# F1C100S-MY.net
KiCad netlist of a schematic drawn in Altium Designer
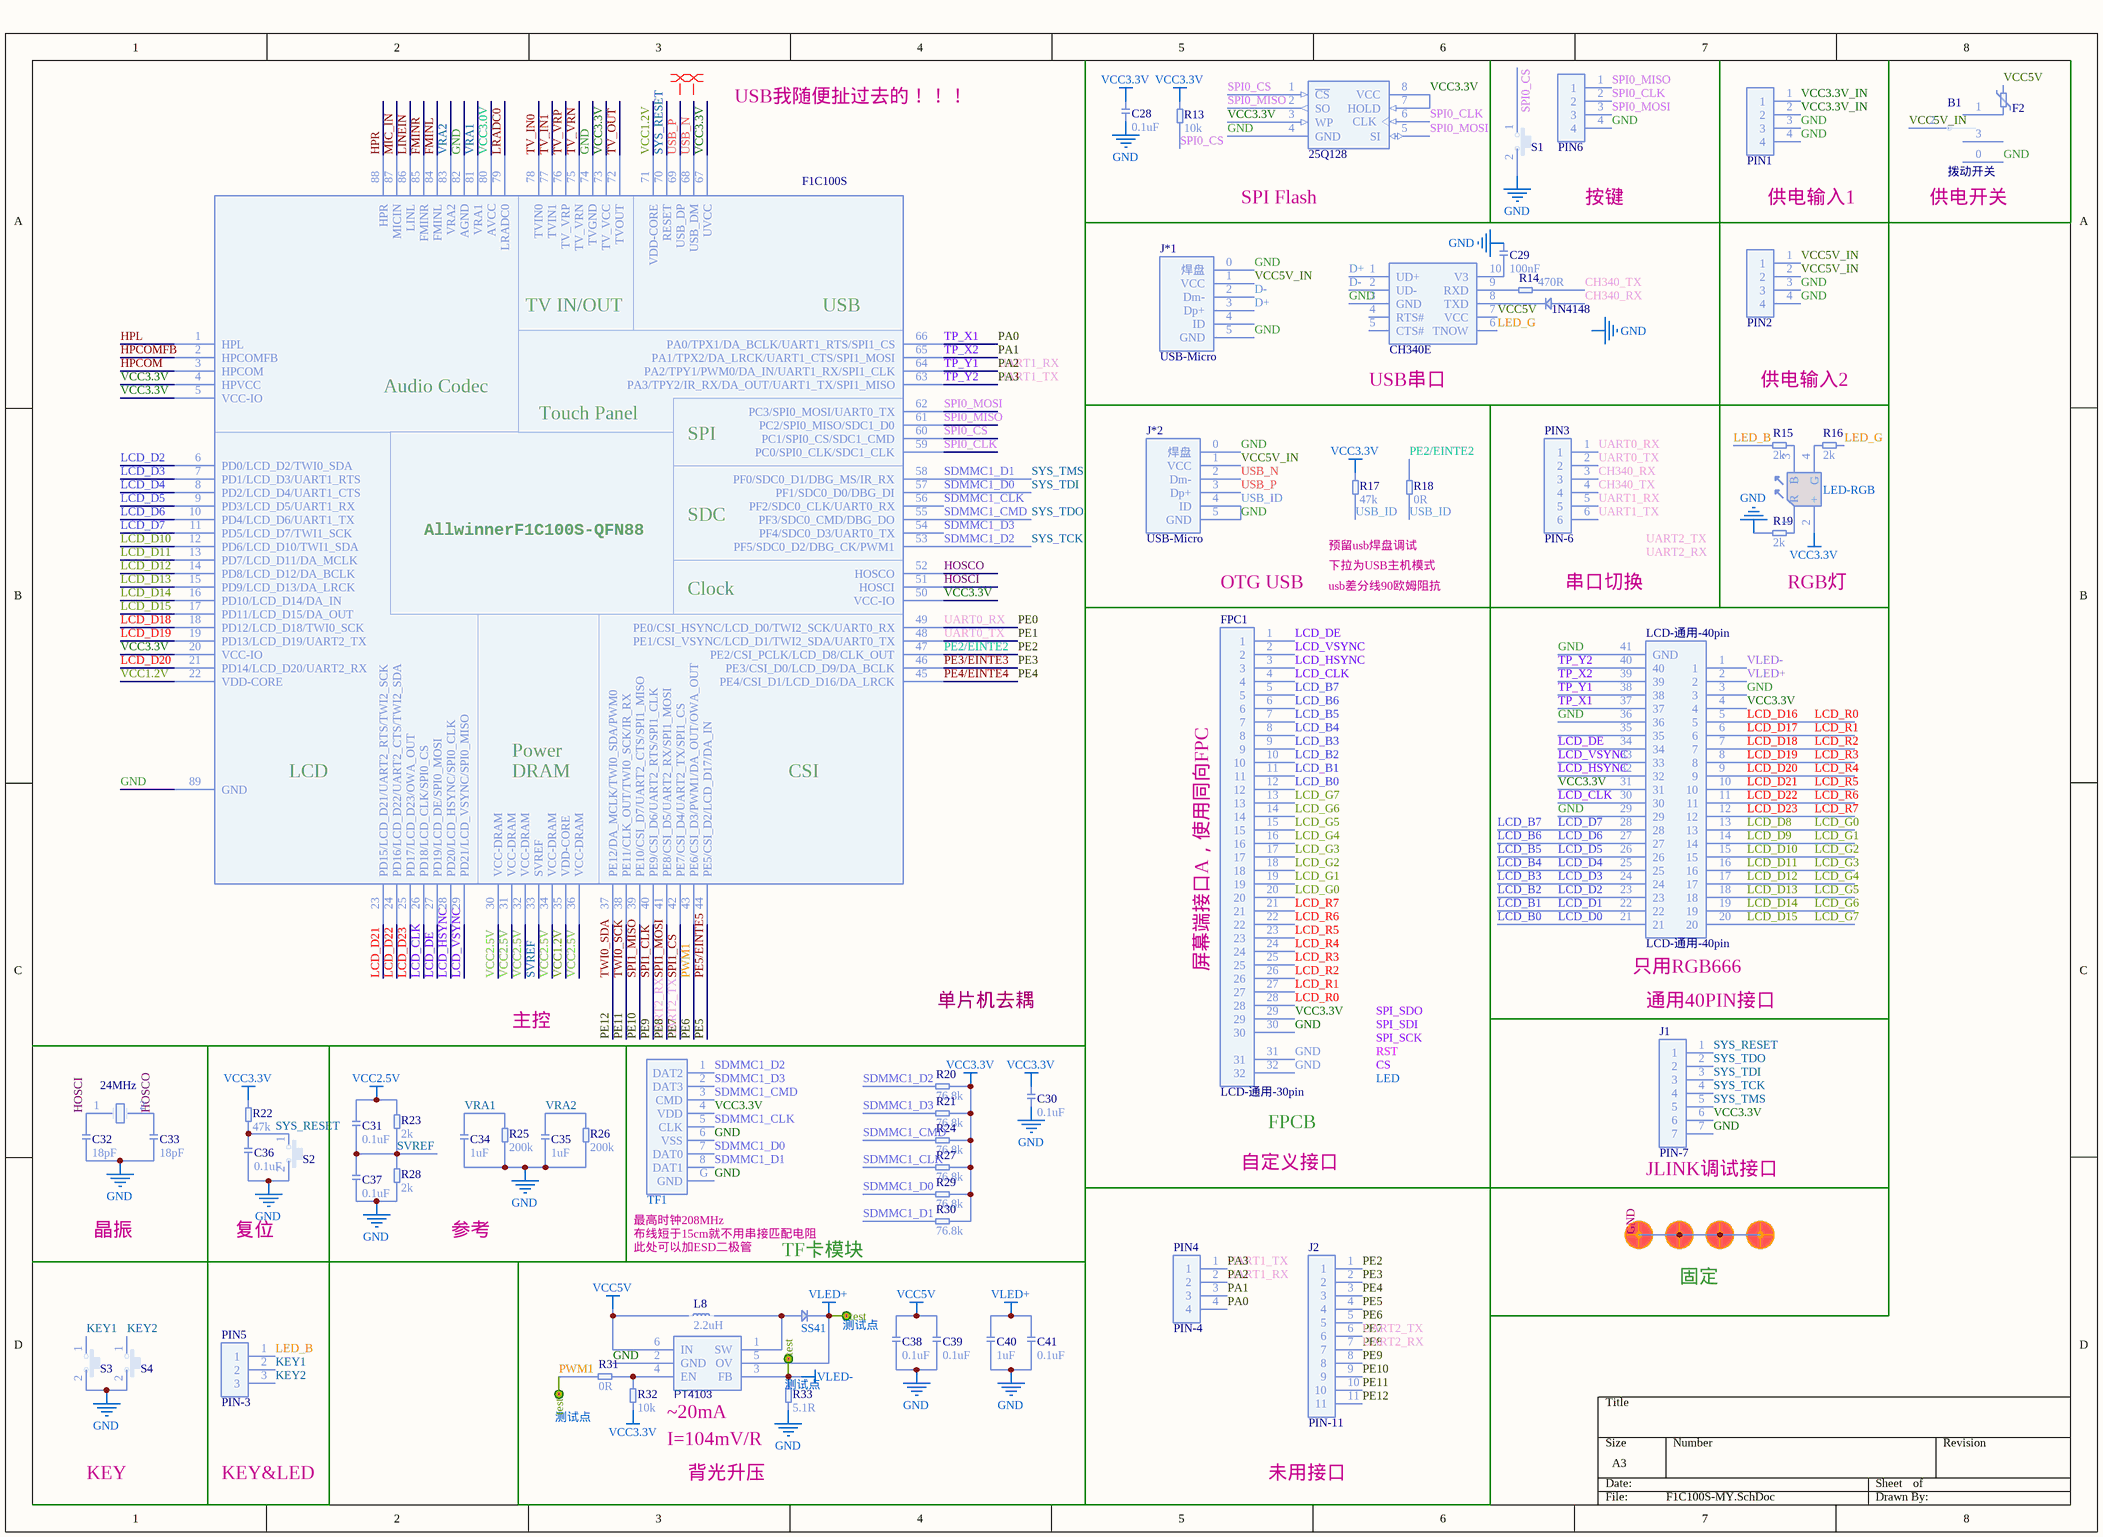
[diagram p0: F1C100S-MY.SchDoc]

(export (version "E")
  (design (tool "Eeschema 10.0.6"))
  (components
    (comp (ref "1N4148") (value "直插1N4148") (footprint "L0603") (libsource (lib "二极管") (part "直插1N4148")))
    (comp (ref "24MHz") (value "XTAL") (footprint "AT26-mini") (libsource (lib "晶振") (part "XTAL")))
    (comp (ref "25Q128")
      (value "25Qxx")
      (footprint "SOP-8M")
      (description "外置EEPROM")
      (libsource (lib "常用芯片") (part "25Qxx"))
    )
    (comp (ref "B1") (value "拨动开关") (footprint "开关:拨动开关-侧位-4.4X8.7MM") (libsource (lib "开关") (part "拨动开关")))
    (comp (ref "C28")
      (value "0.1uF")
      (footprint "0603C-mini")
      (fields (field (name "Comment") "非极性电容"))
      (libsource (lib "电容") (part "非极性电容"))
    )
    (comp (ref "C29")
      (value "100nF")
      (footprint "0603C-mini")
      (fields (field (name "Comment") "非极性电容"))
      (libsource (lib "电容") (part "非极性电容"))
    )
    (comp (ref "C30")
      (value "0.1uF")
      (footprint "0603C-mini")
      (fields (field (name "Comment") "非极性电容"))
      (libsource (lib "电容") (part "非极性电容"))
    )
    (comp (ref "C31")
      (value "0.1uF")
      (footprint "0603C-mini")
      (fields (field (name "Comment") "非极性电容"))
      (libsource (lib "电容") (part "非极性电容"))
    )
    (comp (ref "C32")
      (value "18pF")
      (footprint "0603C-mini")
      (fields (field (name "Comment") "非极性电容"))
      (libsource (lib "电容") (part "非极性电容"))
    )
    (comp (ref "C33")
      (value "18pF")
      (footprint "0603C-mini")
      (fields (field (name "Comment") "非极性电容"))
      (libsource (lib "电容") (part "非极性电容"))
    )
    (comp (ref "C34")
      (value "1uF")
      (footprint "0603C-mini")
      (fields (field (name "Comment") "非极性电容"))
      (libsource (lib "电容") (part "非极性电容"))
    )
    (comp (ref "C35")
      (value "1uF")
      (footprint "0603C-mini")
      (fields (field (name "Comment") "非极性电容"))
      (libsource (lib "电容") (part "非极性电容"))
    )
    (comp (ref "C36")
      (value "0.1uF")
      (footprint "0603C-mini")
      (fields (field (name "Comment") "非极性电容"))
      (libsource (lib "电容") (part "非极性电容"))
    )
    (comp (ref "C37")
      (value "0.1uF")
      (footprint "0603C-mini")
      (fields (field (name "Comment") "非极性电容"))
      (libsource (lib "电容") (part "非极性电容"))
    )
    (comp (ref "C38")
      (value "0.1uF")
      (footprint "0603C-mini")
      (fields (field (name "Comment") "非极性电容"))
      (libsource (lib "电容") (part "非极性电容"))
    )
    (comp (ref "C39")
      (value "0.1uF")
      (footprint "0603C-mini")
      (fields (field (name "Comment") "非极性电容"))
      (libsource (lib "电容") (part "非极性电容"))
    )
    (comp (ref "C40")
      (value "1uF")
      (footprint "0603C-mini")
      (fields (field (name "Comment") "非极性电容"))
      (libsource (lib "电容") (part "非极性电容"))
    )
    (comp (ref "C41")
      (value "0.1uF")
      (footprint "0603C-mini")
      (fields (field (name "Comment") "非极性电容"))
      (libsource (lib "电容") (part "非极性电容"))
    )
    (comp (ref "CH340E")
      (value "USB2UART_CH340E")
      (footprint "MSOP-10")
      (description "USB2UART")
      (libsource (lib "常用芯片") (part "USB2UART_CH340E"))
    )
    (comp (ref "F1C100S")
      (value "Allwinner-F1C100S")
      (footprint "QFN88")
      (libsource (lib "单片机") (part "Allwinner-F1C100S"))
    )
    (comp (ref "F2") (value "自恢复保险丝") (footprint "电阻:FU 0603") (libsource (lib "电阻") (part "自恢复保险丝")))
    (comp (ref "FPC1")
      (value "LCD-通用-30pin")
      (footprint "LCD-翻盖式-30PIN-0.5MM-2")
      (libsource (lib "LCD-通用") (part "LCD-通用-30pin"))
    )
    (comp (ref "J*1")
      (value "USB-Micro")
      (footprint "USB-MICRO贴片")
      (libsource (lib "接插件") (part "USB-Micro"))
    )
    (comp (ref "J*2")
      (value "USB-Micro")
      (footprint "USB-MICRO贴片")
      (libsource (lib "接插件") (part "USB-Micro"))
    )
    (comp (ref "J1") (value "PIN-7") (footprint "2.54排针1X7-标准") (libsource (lib "接插件") (part "PIN-7")))
    (comp (ref "J2") (value "PIN-11") (footprint "2.54排针1X11-标准") (libsource (lib "接插件") (part "PIN-11")))
    (comp (ref "J3") (value "定位孔") (footprint "定位孔 - 1.9MM") (libsource (lib "接插件") (part "定位孔")))
    (comp (ref "J4") (value "定位孔") (footprint "定位孔 - 1.9MM") (libsource (lib "接插件") (part "定位孔")))
    (comp (ref "J5") (value "定位孔") (footprint "定位孔 - 1.9MM") (libsource (lib "接插件") (part "定位孔")))
    (comp (ref "J6") (value "定位孔") (footprint "定位孔 - 1.9MM") (libsource (lib "接插件") (part "定位孔")))
    (comp (ref "L8")
      (value "2.2uH")
      (footprint "SMD-4.5x4.0x3.2mm")
      (fields (field (name "Comment") "贴片电感"))
      (libsource (lib "电感") (part "贴片电感"))
    )
    (comp (ref "LCD-通用-40pin")
      (value "LCD-通用-40pin")
      (footprint "LCD-翻盖式-40PIN-0.5MM-2")
      (libsource (lib "LCD-通用") (part "LCD-通用-40pin"))
    )
    (comp (ref "LED-RGB") (value "0606 RGB") (footprint "0606RGB") (libsource (lib "二极管") (part "0606 RGB")))
    (comp (ref "PIN1") (value "PIN-4") (footprint "2.54排针2X2-标准") (libsource (lib "接插件") (part "PIN-4")))
    (comp (ref "PIN2") (value "PIN-4") (footprint "2.54排针2X2-标准") (libsource (lib "接插件") (part "PIN-4")))
    (comp (ref "PIN3") (value "PIN-6") (footprint "2.54排针2X3-标准") (libsource (lib "接插件") (part "PIN-6")))
    (comp (ref "PIN4") (value "PIN-4") (footprint "2.54排针1X4-标准") (libsource (lib "接插件") (part "PIN-4")))
    (comp (ref "PIN5") (value "PIN-3") (footprint "2.54排针1X3-标准") (libsource (lib "接插件") (part "PIN-3")))
    (comp (ref "PIN6") (value "PIN-4") (footprint "2.54排针1X4-标准") (libsource (lib "接插件") (part "PIN-4")))
    (comp (ref "PT4103")
      (value "DCDC_PT4103")
      (footprint "SOT-23-6")
      (description "升压型DCDC")
      (libsource (lib "常用芯片") (part "DCDC_PT4103"))
    )
    (comp (ref "R13")
      (value "10k")
      (footprint "R0603-mini")
      (description "贴片电阻")
      (libsource (lib "") (part "贴片电阻_1"))
    )
    (comp (ref "R14")
      (value "470R")
      (footprint "R0603-mini")
      (description "贴片电阻")
      (libsource (lib "电阻") (part "贴片电阻"))
    )
    (comp (ref "R15")
      (value "2k")
      (footprint "R0603-mini")
      (description "贴片电阻")
      (libsource (lib "") (part "贴片电阻_3"))
    )
    (comp (ref "R16")
      (value "2k")
      (footprint "R0603-mini")
      (description "贴片电阻")
      (libsource (lib "电阻") (part "贴片电阻"))
    )
    (comp (ref "R17")
      (value "47k")
      (footprint "R0603-mini")
      (description "贴片电阻")
      (libsource (lib "") (part "贴片电阻_1"))
    )
    (comp (ref "R18")
      (value "0R")
      (footprint "R0603-mini")
      (description "贴片电阻")
      (libsource (lib "") (part "贴片电阻_1"))
    )
    (comp (ref "R19")
      (value "2k")
      (footprint "R0603-mini")
      (description "贴片电阻")
      (libsource (lib "") (part "贴片电阻_3"))
    )
    (comp (ref "R20")
      (value "76.8k")
      (footprint "R0603-non")
      (description "贴片电阻")
      (libsource (lib "电阻") (part "贴片电阻"))
    )
    (comp (ref "R21")
      (value "76.8k")
      (footprint "R0603-non")
      (description "贴片电阻")
      (libsource (lib "电阻") (part "贴片电阻"))
    )
    (comp (ref "R22")
      (value "47k")
      (footprint "R0603-mini")
      (description "贴片电阻")
      (libsource (lib "") (part "贴片电阻_1"))
    )
    (comp (ref "R23")
      (value "2k")
      (footprint "R0603-mini")
      (description "贴片电阻")
      (libsource (lib "") (part "贴片电阻_2"))
    )
    (comp (ref "R24")
      (value "76.8k")
      (footprint "R0603-non")
      (description "贴片电阻")
      (libsource (lib "电阻") (part "贴片电阻"))
    )
    (comp (ref "R25")
      (value "200k")
      (footprint "R0603-mini")
      (description "贴片电阻")
      (libsource (lib "") (part "贴片电阻_2"))
    )
    (comp (ref "R26")
      (value "200k")
      (footprint "R0603-mini")
      (description "贴片电阻")
      (libsource (lib "") (part "贴片电阻_2"))
    )
    (comp (ref "R27")
      (value "76.8k")
      (footprint "R0603-non")
      (description "贴片电阻")
      (libsource (lib "电阻") (part "贴片电阻"))
    )
    (comp (ref "R28")
      (value "2k")
      (footprint "R0603-mini")
      (description "贴片电阻")
      (libsource (lib "") (part "贴片电阻_2"))
    )
    (comp (ref "R29")
      (value "76.8k")
      (footprint "R0603-non")
      (description "贴片电阻")
      (libsource (lib "电阻") (part "贴片电阻"))
    )
    (comp (ref "R30")
      (value "76.8k")
      (footprint "R0603-non")
      (description "贴片电阻")
      (libsource (lib "电阻") (part "贴片电阻"))
    )
    (comp (ref "R31")
      (value "0R")
      (footprint "R0603-mini")
      (description "贴片电阻")
      (libsource (lib "") (part "贴片电阻_3"))
    )
    (comp (ref "R32")
      (value "10k")
      (footprint "R0603-mini")
      (description "贴片电阻")
      (libsource (lib "") (part "贴片电阻_2"))
    )
    (comp (ref "R33")
      (value "5.1R")
      (footprint "R0603-mini")
      (description "贴片电阻")
      (libsource (lib "") (part "贴片电阻_2"))
    )
    (comp (ref "S1")
      (value "微动开关2P")
      (footprint "开关:贴片按键微动开关-3*6*2.5")
      (libsource (lib "开关") (part "微动开关2P"))
    )
    (comp (ref "S2")
      (value "微动开关2P")
      (footprint "开关:贴片按键微动开关-3*6*2.5")
      (libsource (lib "开关") (part "微动开关2P"))
    )
    (comp (ref "S3")
      (value "微动开关2P")
      (footprint "开关:贴片按键微动开关-3*6*2.5")
      (libsource (lib "开关") (part "微动开关2P"))
    )
    (comp (ref "S4")
      (value "微动开关2P")
      (footprint "开关:贴片按键微动开关-3*6*2.5")
      (libsource (lib "开关") (part "微动开关2P"))
    )
    (comp (ref "SS41") (value "肖特基二极管") (footprint "SMA(DO-214AC)") (libsource (lib "二极管") (part "肖特基二极管")))
    (comp (ref "test7") (value "测试点") (footprint "测试点30mil") (libsource (lib "接插件") (part "测试点")))
    (comp (ref "test8") (value "测试点") (footprint "测试点30mil") (libsource (lib "接插件") (part "测试点")))
    (comp (ref "test9") (value "测试点") (footprint "测试点30mil") (libsource (lib "接插件") (part "测试点")))
    (comp (ref "TF1") (value "TF卡座") (footprint "TF卡座C") (libsource (lib "接插件") (part "TF卡座2")))
  )
  (nets
    (net (code "1") (name "/CH340_RX") (class "Default")
      (node (ref "1N4148") (pin "1") (pinfunction "1_1") (pintype "passive"))
      (node (ref "PIN3") (pin "3") (pinfunction "3_3") (pintype "passive"))
    )
    (net (code "2") (name "/CH340_TX") (class "Default")
      (node (ref "PIN3") (pin "4") (pinfunction "4_4") (pintype "passive"))
      (node (ref "R14") (pin "2") (pinfunction "2_2") (pintype "passive"))
    )
    (net (code "4") (name "/D+") (class "Default")
      (node (ref "CH340E") (pin "1") (pinfunction "UD+_1") (pintype "passive"))
      (node (ref "J*1") (pin "3") (pinfunction "Dp+_3") (pintype "passive"))
    )
    (net (code "5") (name "/D-") (class "Default")
      (node (ref "CH340E") (pin "2") (pinfunction "UD-_2") (pintype "passive"))
      (node (ref "J*1") (pin "2") (pinfunction "Dm-_2") (pintype "passive"))
    )
    (net (code "6") (name "/FMINL") (class "Default")
      (node (ref "F1C100S") (pin "84") (pinfunction "FMINL_84") (pintype "passive"))
    )
    (net (code "7") (name "/FMINR") (class "Default")
      (node (ref "F1C100S") (pin "85") (pinfunction "FMINR_85") (pintype "passive"))
    )
    (net (code "9") (name "/HOSCI") (class "Default")
      (node (ref "24MHz") (pin "1") (pinfunction "1_1") (pintype "passive"))
      (node (ref "C32") (pin "2") (pinfunction "2_2") (pintype "passive"))
      (node (ref "F1C100S") (pin "51") (pinfunction "HOSCI_51") (pintype "passive"))
    )
    (net (code "10") (name "/HOSCO") (class "Default")
      (node (ref "24MHz") (pin "2") (pinfunction "2_2") (pintype "passive"))
      (node (ref "C33") (pin "2") (pinfunction "2_2") (pintype "passive"))
      (node (ref "F1C100S") (pin "52") (pinfunction "HOSCO_52") (pintype "passive"))
    )
    (net (code "11") (name "/HPCOM") (class "Default")
      (node (ref "F1C100S") (pin "3") (pinfunction "HPCOM_3") (pintype "passive"))
    )
    (net (code "12") (name "/HPCOMFB") (class "Default")
      (node (ref "F1C100S") (pin "2") (pinfunction "HPCOMFB_2") (pintype "passive"))
    )
    (net (code "13") (name "/HPL") (class "Default")
      (node (ref "F1C100S") (pin "1") (pinfunction "HPL_1") (pintype "passive"))
    )
    (net (code "14") (name "/HPR") (class "Default")
      (node (ref "F1C100S") (pin "88") (pinfunction "HPR_88") (pintype "passive"))
    )
    (net (code "16") (name "/KEY1") (class "Default")
      (node (ref "PIN5") (pin "2") (pinfunction "2_2") (pintype "passive"))
      (node (ref "S3") (pin "1") (pinfunction "1_1") (pintype "passive"))
    )
    (net (code "17") (name "/KEY2") (class "Default")
      (node (ref "PIN5") (pin "3") (pinfunction "3_3") (pintype "passive"))
      (node (ref "S4") (pin "1") (pinfunction "1_1") (pintype "passive"))
    )
    (net (code "18") (name "/LCD_B0") (class "Default")
      (node (ref "FPC1") (pin "12") (pinfunction "12_12") (pintype "passive"))
      (node (ref "LCD-通用-40pin") (pin "21") (pinfunction "21_21") (pintype "passive"))
    )
    (net (code "19") (name "/LCD_B1") (class "Default")
      (node (ref "FPC1") (pin "11") (pinfunction "11_11") (pintype "passive"))
      (node (ref "LCD-通用-40pin") (pin "22") (pinfunction "22_22") (pintype "passive"))
    )
    (net (code "20") (name "/LCD_B2") (class "Default")
      (node (ref "F1C100S") (pin "6") (pinfunction "PD0/LCD_D2/TWI0_SDA_6") (pintype "passive"))
      (node (ref "FPC1") (pin "10") (pinfunction "10_10") (pintype "passive"))
      (node (ref "LCD-通用-40pin") (pin "23") (pinfunction "23_23") (pintype "passive"))
    )
    (net (code "21") (name "/LCD_B3") (class "Default")
      (node (ref "F1C100S") (pin "7") (pinfunction "PD1/LCD_D3/UART1_RTS_7") (pintype "passive"))
      (node (ref "FPC1") (pin "9") (pinfunction "9_9") (pintype "passive"))
      (node (ref "LCD-通用-40pin") (pin "24") (pinfunction "24_24") (pintype "passive"))
    )
    (net (code "22") (name "/LCD_B4") (class "Default")
      (node (ref "F1C100S") (pin "8") (pinfunction "PD2/LCD_D4/UART1_CTS_8") (pintype "passive"))
      (node (ref "FPC1") (pin "8") (pinfunction "8_8") (pintype "passive"))
      (node (ref "LCD-通用-40pin") (pin "25") (pinfunction "25_25") (pintype "passive"))
    )
    (net (code "23") (name "/LCD_B5") (class "Default")
      (node (ref "F1C100S") (pin "9") (pinfunction "PD3/LCD_D5/UART1_RX_9") (pintype "passive"))
      (node (ref "FPC1") (pin "7") (pinfunction "7_7") (pintype "passive"))
      (node (ref "LCD-通用-40pin") (pin "26") (pinfunction "26_26") (pintype "passive"))
    )
    (net (code "24") (name "/LCD_B6") (class "Default")
      (node (ref "F1C100S") (pin "10") (pinfunction "PD4/LCD_D6/UART1_TX_10") (pintype "passive"))
      (node (ref "FPC1") (pin "6") (pinfunction "6_6") (pintype "passive"))
      (node (ref "LCD-通用-40pin") (pin "27") (pinfunction "27_27") (pintype "passive"))
    )
    (net (code "25") (name "/LCD_B7") (class "Default")
      (node (ref "F1C100S") (pin "11") (pinfunction "PD5/LCD_D7/TWI1_SCK_11") (pintype "passive"))
      (node (ref "FPC1") (pin "5") (pinfunction "5_5") (pintype "passive"))
      (node (ref "LCD-通用-40pin") (pin "28") (pinfunction "28_28") (pintype "passive"))
    )
    (net (code "26") (name "/LCD_CLK") (class "Default")
      (node (ref "F1C100S") (pin "26") (pinfunction "PD18/LCD_CLK/SPI0_CS_26") (pintype "passive"))
      (node (ref "FPC1") (pin "4") (pinfunction "4_4") (pintype "passive"))
      (node (ref "LCD-通用-40pin") (pin "30") (pinfunction "30_30") (pintype "passive"))
    )
    (net (code "27") (name "/LCD_D8") (class "Default")
      (node (ref "FPC1") (pin "20") (pinfunction "20_20") (pintype "passive"))
      (node (ref "LCD-通用-40pin") (pin "13") (pinfunction "13_13") (pintype "passive"))
    )
    (net (code "28") (name "/LCD_D9") (class "Default")
      (node (ref "FPC1") (pin "19") (pinfunction "19_19") (pintype "passive"))
      (node (ref "LCD-通用-40pin") (pin "14") (pinfunction "14_14") (pintype "passive"))
    )
    (net (code "29") (name "/LCD_D10") (class "Default")
      (node (ref "F1C100S") (pin "12") (pinfunction "PD6/LCD_D10/TWI1_SDA_12") (pintype "passive"))
      (node (ref "FPC1") (pin "18") (pinfunction "18_18") (pintype "passive"))
      (node (ref "LCD-通用-40pin") (pin "15") (pinfunction "15_15") (pintype "passive"))
    )
    (net (code "30") (name "/LCD_D11") (class "Default")
      (node (ref "F1C100S") (pin "13") (pinfunction "PD7/LCD_D11/DA_MCLK_13") (pintype "passive"))
      (node (ref "FPC1") (pin "17") (pinfunction "17_17") (pintype "passive"))
      (node (ref "LCD-通用-40pin") (pin "16") (pinfunction "16_16") (pintype "passive"))
    )
    (net (code "31") (name "/LCD_D12") (class "Default")
      (node (ref "F1C100S") (pin "14") (pinfunction "PD8/LCD_D12/DA_BCLK_14") (pintype "passive"))
      (node (ref "FPC1") (pin "16") (pinfunction "16_16") (pintype "passive"))
      (node (ref "LCD-通用-40pin") (pin "17") (pinfunction "17_17") (pintype "passive"))
    )
    (net (code "32") (name "/LCD_D13") (class "Default")
      (node (ref "F1C100S") (pin "15") (pinfunction "PD9/LCD_D13/DA_LRCK_15") (pintype "passive"))
      (node (ref "FPC1") (pin "15") (pinfunction "15_15") (pintype "passive"))
      (node (ref "LCD-通用-40pin") (pin "18") (pinfunction "18_18") (pintype "passive"))
    )
    (net (code "33") (name "/LCD_D14") (class "Default")
      (node (ref "F1C100S") (pin "16") (pinfunction "PD10/LCD_D14/DA_IN_16") (pintype "passive"))
      (node (ref "FPC1") (pin "14") (pinfunction "14_14") (pintype "passive"))
      (node (ref "LCD-通用-40pin") (pin "19") (pinfunction "19_19") (pintype "passive"))
    )
    (net (code "34") (name "/LCD_D15") (class "Default")
      (node (ref "F1C100S") (pin "17") (pinfunction "PD11/LCD_D15/DA_OUT_17") (pintype "passive"))
      (node (ref "FPC1") (pin "13") (pinfunction "13_13") (pintype "passive"))
      (node (ref "LCD-通用-40pin") (pin "20") (pinfunction "20_20") (pintype "passive"))
    )
    (net (code "35") (name "/LCD_D16") (class "Default")
      (node (ref "FPC1") (pin "28") (pinfunction "28_28") (pintype "passive"))
      (node (ref "LCD-通用-40pin") (pin "5") (pinfunction "5_5") (pintype "passive"))
    )
    (net (code "36") (name "/LCD_D17") (class "Default")
      (node (ref "FPC1") (pin "27") (pinfunction "27_27") (pintype "passive"))
      (node (ref "LCD-通用-40pin") (pin "6") (pinfunction "6_6") (pintype "passive"))
    )
    (net (code "37") (name "/LCD_D18") (class "Default")
      (node (ref "F1C100S") (pin "18") (pinfunction "PD12/LCD_D18/TWI0_SCK_18") (pintype "passive"))
      (node (ref "FPC1") (pin "26") (pinfunction "26_26") (pintype "passive"))
      (node (ref "LCD-通用-40pin") (pin "7") (pinfunction "7_7") (pintype "passive"))
    )
    (net (code "38") (name "/LCD_D19") (class "Default")
      (node (ref "F1C100S") (pin "19") (pinfunction "PD13/LCD_D19/UART2_TX_19") (pintype "passive"))
      (node (ref "FPC1") (pin "25") (pinfunction "25_25") (pintype "passive"))
      (node (ref "LCD-通用-40pin") (pin "8") (pinfunction "8_8") (pintype "passive"))
    )
    (net (code "39") (name "/LCD_D20") (class "Default")
      (node (ref "F1C100S") (pin "21") (pinfunction "PD14/LCD_D20/UART2_RX_21") (pintype "passive"))
      (node (ref "FPC1") (pin "24") (pinfunction "24_24") (pintype "passive"))
      (node (ref "LCD-通用-40pin") (pin "9") (pinfunction "9_9") (pintype "passive"))
    )
    (net (code "40") (name "/LCD_D21") (class "Default")
      (node (ref "F1C100S") (pin "23") (pinfunction "PD15/LCD_D21/UART2_RTS/TWI2_SCK_23") (pintype "passive"))
      (node (ref "FPC1") (pin "23") (pinfunction "23_23") (pintype "passive"))
      (node (ref "LCD-通用-40pin") (pin "10") (pinfunction "10_10") (pintype "passive"))
    )
    (net (code "41") (name "/LCD_D22") (class "Default")
      (node (ref "F1C100S") (pin "24") (pinfunction "PD16/LCD_D22/UART2_CTS/TWI2_SDA_24") (pintype "passive"))
      (node (ref "FPC1") (pin "22") (pinfunction "22_22") (pintype "passive"))
      (node (ref "LCD-通用-40pin") (pin "11") (pinfunction "11_11") (pintype "passive"))
    )
    (net (code "42") (name "/LCD_D23") (class "Default")
      (node (ref "F1C100S") (pin "25") (pinfunction "PD17/LCD_D23/OWA_OUT_25") (pintype "passive"))
      (node (ref "FPC1") (pin "21") (pinfunction "21_21") (pintype "passive"))
      (node (ref "LCD-通用-40pin") (pin "12") (pinfunction "12_12") (pintype "passive"))
    )
    (net (code "43") (name "/LCD_DE") (class "Default")
      (node (ref "F1C100S") (pin "27") (pinfunction "PD19/LCD_DE/SPI0_MOSI_27") (pintype "passive"))
      (node (ref "FPC1") (pin "1") (pinfunction "1_1") (pintype "passive"))
      (node (ref "LCD-通用-40pin") (pin "34") (pinfunction "34_34") (pintype "passive"))
    )
    (net (code "44") (name "/LCD_HSYNC") (class "Default")
      (node (ref "F1C100S") (pin "28") (pinfunction "PD20/LCD_HSYNC/SPI0_CLK_28") (pintype "passive"))
      (node (ref "FPC1") (pin "3") (pinfunction "3_3") (pintype "passive"))
      (node (ref "LCD-通用-40pin") (pin "32") (pinfunction "32_32") (pintype "passive"))
    )
    (net (code "45") (name "/LCD_VSYNC") (class "Default")
      (node (ref "F1C100S") (pin "29") (pinfunction "PD21/LCD_VSYNC/SPI0_MISO_29") (pintype "passive"))
      (node (ref "FPC1") (pin "2") (pinfunction "2_2") (pintype "passive"))
      (node (ref "LCD-通用-40pin") (pin "33") (pinfunction "33_33") (pintype "passive"))
    )
    (net (code "47") (name "/LED_B") (class "Default")
      (node (ref "PIN5") (pin "1") (pinfunction "1_1") (pintype "passive"))
      (node (ref "R15") (pin "2") (pinfunction "2_2") (pintype "passive"))
    )
    (net (code "48") (name "/LED_G") (class "Default")
      (node (ref "CH340E") (pin "6") (pinfunction "TNOW_6") (pintype "passive"))
      (node (ref "R16") (pin "2") (pinfunction "2_2") (pintype "passive"))
    )
    (net (code "49") (name "/LINEIN") (class "Default")
      (node (ref "F1C100S") (pin "86") (pinfunction "LINL_86") (pintype "passive"))
    )
    (net (code "50") (name "/LRADC0") (class "Default")
      (node (ref "F1C100S") (pin "79") (pinfunction "LRADC0_79") (pintype "passive"))
    )
    (net (code "51") (name "/MIC_IN") (class "Default")
      (node (ref "F1C100S") (pin "87") (pinfunction "MICIN_87") (pintype "passive"))
    )
    (net (code "52") (name "/PA0") (class "Default")
      (node (ref "F1C100S") (pin "66") (pinfunction "PA0/TPX1/DA_BCLK/UART1_RTS/SPI1_CS_66") (pintype "passive"))
      (node (ref "LCD-通用-40pin") (pin "37") (pinfunction "37_37") (pintype "passive"))
      (node (ref "PIN4") (pin "4") (pinfunction "4_4") (pintype "passive"))
    )
    (net (code "53") (name "/PA1") (class "Default")
      (node (ref "F1C100S") (pin "65") (pinfunction "PA1/TPX2/DA_LRCK/UART1_CTS/SPI1_MOSI_65") (pintype "passive"))
      (node (ref "LCD-通用-40pin") (pin "39") (pinfunction "39_39") (pintype "passive"))
      (node (ref "PIN4") (pin "3") (pinfunction "3_3") (pintype "passive"))
    )
    (net (code "54") (name "/PA2") (class "Default")
      (node (ref "F1C100S") (pin "64") (pinfunction "PA2/TPY1/PWM0/DA_IN/UART1_RX/SPI1_CLK_64") (pintype "passive"))
      (node (ref "LCD-通用-40pin") (pin "38") (pinfunction "38_38") (pintype "passive"))
      (node (ref "PIN3") (pin "5") (pinfunction "5_5") (pintype "passive"))
      (node (ref "PIN4") (pin "2") (pinfunction "2_2") (pintype "passive"))
    )
    (net (code "55") (name "/PA3") (class "Default")
      (node (ref "F1C100S") (pin "63") (pinfunction "PA3/TPY2/IR_RX/DA_OUT/UART1_TX/SPI1_MISO_63") (pintype "passive"))
      (node (ref "LCD-通用-40pin") (pin "40") (pinfunction "40_40") (pintype "passive"))
      (node (ref "PIN3") (pin "6") (pinfunction "6_6") (pintype "passive"))
      (node (ref "PIN4") (pin "1") (pinfunction "1_1") (pintype "passive"))
    )
    (net (code "56") (name "/PE0") (class "Default")
      (node (ref "F1C100S") (pin "49") (pinfunction "PE0/CSI_HSYNC/LCD_D0/TWI2_SCK/UART0_RX_49") (pintype "passive"))
      (node (ref "PIN3") (pin "1") (pinfunction "1_1") (pintype "passive"))
    )
    (net (code "57") (name "/PE1") (class "Default")
      (node (ref "F1C100S") (pin "48") (pinfunction "PE1/CSI_VSYNC/LCD_D1/TWI2_SDA/UART0_TX_48") (pintype "passive"))
      (node (ref "PIN3") (pin "2") (pinfunction "2_2") (pintype "passive"))
    )
    (net (code "58") (name "/PE2") (class "Default")
      (node (ref "F1C100S") (pin "47") (pinfunction "PE2/CSI_PCLK/LCD_D8/CLK_OUT_47") (pintype "passive"))
      (node (ref "J2") (pin "1") (pinfunction "1_1") (pintype "passive"))
      (node (ref "R18") (pin "1") (pinfunction "1_1") (pintype "passive"))
    )
    (net (code "59") (name "/PE3") (class "Default")
      (node (ref "F1C100S") (pin "46") (pinfunction "PE3/CSI_D0/LCD_D9/DA_BCLK_46") (pintype "passive"))
      (node (ref "J2") (pin "2") (pinfunction "2_2") (pintype "passive"))
    )
    (net (code "60") (name "/PE4") (class "Default")
      (node (ref "F1C100S") (pin "45") (pinfunction "PE4/CSI_D1/LCD_D16/DA_LRCK_45") (pintype "passive"))
      (node (ref "J2") (pin "3") (pinfunction "3_3") (pintype "passive"))
    )
    (net (code "61") (name "/PE5") (class "Default")
      (node (ref "F1C100S") (pin "44") (pinfunction "PE5/CSI_D2/LCD_D17/DA_IN_44") (pintype "passive"))
      (node (ref "J2") (pin "4") (pinfunction "4_4") (pintype "passive"))
    )
    (net (code "62") (name "/PE6") (class "Default")
      (node (ref "F1C100S") (pin "43") (pinfunction "PE6/CSI_D3/PWM1/DA_OUT/OWA_OUT_43") (pintype "passive"))
      (node (ref "J2") (pin "5") (pinfunction "5_5") (pintype "passive"))
      (node (ref "R31") (pin "2") (pinfunction "2_2") (pintype "passive"))
      (node (ref "test9") (pin "1") (pinfunction "test_1") (pintype "passive"))
    )
    (net (code "63") (name "/PE7") (class "Default")
      (node (ref "F1C100S") (pin "42") (pinfunction "PE7/CSI_D4/UART2_TX/SPI1_CS_42") (pintype "passive"))
      (node (ref "J2") (pin "6") (pinfunction "6_6") (pintype "passive"))
    )
    (net (code "64") (name "/PE8") (class "Default")
      (node (ref "F1C100S") (pin "41") (pinfunction "PE8/CSI_D5/UART2_RX/SPI1_MOSI_41") (pintype "passive"))
      (node (ref "J2") (pin "7") (pinfunction "7_7") (pintype "passive"))
    )
    (net (code "65") (name "/PE9") (class "Default")
      (node (ref "F1C100S") (pin "40") (pinfunction "PE9/CSI_D6/UART2_RTS/SPI1_CLK_40") (pintype "passive"))
      (node (ref "J2") (pin "8") (pinfunction "8_8") (pintype "passive"))
    )
    (net (code "66") (name "/PE10") (class "Default")
      (node (ref "F1C100S") (pin "39") (pinfunction "PE10/CSI_D7/UART2_CTS/SPI1_MISO_39") (pintype "passive"))
      (node (ref "J2") (pin "9") (pinfunction "9_9") (pintype "passive"))
    )
    (net (code "67") (name "/PE11") (class "Default")
      (node (ref "F1C100S") (pin "38") (pinfunction "PE11/CLK_OUT/TWI0_SCK/IR_RX_38") (pintype "passive"))
      (node (ref "J2") (pin "10") (pinfunction "10_10") (pintype "passive"))
    )
    (net (code "68") (name "/PE12") (class "Default")
      (node (ref "F1C100S") (pin "37") (pinfunction "PE12/DA_MCLK/TWI0_SDA/PWM0_37") (pintype "passive"))
      (node (ref "J2") (pin "11") (pinfunction "11_11") (pintype "passive"))
    )
    (net (code "70") (name "/SDMMC1_CLK") (class "Default")
      (node (ref "F1C100S") (pin "56") (pinfunction "PF2/SDC0_CLK/UART0_RX_56") (pintype "passive"))
      (node (ref "R27") (pin "1") (pinfunction "1_1") (pintype "passive"))
      (node (ref "TF1") (pin "5") (pinfunction "CLK_5") (pintype "passive"))
    )
    (net (code "71") (name "/SDMMC1_CMD") (class "Default")
      (node (ref "F1C100S") (pin "55") (pinfunction "PF3/SDC0_CMD/DBG_DO_55") (pintype "passive"))
      (node (ref "J1") (pin "2") (pinfunction "2_2") (pintype "passive"))
      (node (ref "R24") (pin "1") (pinfunction "1_1") (pintype "passive"))
      (node (ref "TF1") (pin "3") (pinfunction "CMD_3") (pintype "passive"))
    )
    (net (code "72") (name "/SDMMC1_D0") (class "Default")
      (node (ref "F1C100S") (pin "57") (pinfunction "PF1/SDC0_D0/DBG_DI_57") (pintype "passive"))
      (node (ref "J1") (pin "3") (pinfunction "3_3") (pintype "passive"))
      (node (ref "R29") (pin "1") (pinfunction "1_1") (pintype "passive"))
      (node (ref "TF1") (pin "7") (pinfunction "DAT0_7") (pintype "passive"))
    )
    (net (code "73") (name "/SDMMC1_D1") (class "Default")
      (node (ref "F1C100S") (pin "58") (pinfunction "PF0/SDC0_D1/DBG_MS/IR_RX_58") (pintype "passive"))
      (node (ref "J1") (pin "5") (pinfunction "5_5") (pintype "passive"))
      (node (ref "R30") (pin "1") (pinfunction "1_1") (pintype "passive"))
      (node (ref "TF1") (pin "8") (pinfunction "DAT1_8") (pintype "passive"))
    )
    (net (code "74") (name "/SDMMC1_D2") (class "Default")
      (node (ref "F1C100S") (pin "53") (pinfunction "PF5/SDC0_D2/DBG_CK/PWM1_53") (pintype "passive"))
      (node (ref "J1") (pin "4") (pinfunction "4_4") (pintype "passive"))
      (node (ref "R20") (pin "1") (pinfunction "1_1") (pintype "passive"))
      (node (ref "TF1") (pin "1") (pinfunction "DAT2_1") (pintype "passive"))
    )
    (net (code "75") (name "/SDMMC1_D3") (class "Default")
      (node (ref "F1C100S") (pin "54") (pinfunction "PF4/SDC0_D3/UART0_TX_54") (pintype "passive"))
      (node (ref "R21") (pin "1") (pinfunction "1_1") (pintype "passive"))
      (node (ref "TF1") (pin "2") (pinfunction "DAT3_2") (pintype "passive"))
    )
    (net (code "76") (name "/SPI0_CLK") (class "Default")
      (node (ref "25Q128") (pin "6") (pinfunction "CLK_6") (pintype "input"))
      (node (ref "F1C100S") (pin "59") (pinfunction "PC0/SPI0_CLK/SDC1_CLK_59") (pintype "passive"))
      (node (ref "PIN6") (pin "2") (pinfunction "2_2") (pintype "passive"))
    )
    (net (code "77") (name "/SPI0_CS") (class "Default")
      (node (ref "25Q128") (pin "1") (pinfunction "~{CS}_1") (pintype "input"))
      (node (ref "F1C100S") (pin "60") (pinfunction "PC1/SPI0_CS/SDC1_CMD_60") (pintype "passive"))
      (node (ref "R13") (pin "2") (pinfunction "2_2") (pintype "passive"))
      (node (ref "S1") (pin "1") (pinfunction "1_1") (pintype "passive"))
    )
    (net (code "78") (name "/SPI0_MISO") (class "Default")
      (node (ref "25Q128") (pin "2") (pinfunction "SO_2") (pintype "output"))
      (node (ref "F1C100S") (pin "61") (pinfunction "PC2/SPI0_MISO/SDC1_D0_61") (pintype "passive"))
      (node (ref "PIN6") (pin "1") (pinfunction "1_1") (pintype "passive"))
    )
    (net (code "79") (name "/SPI0_MOSI") (class "Default")
      (node (ref "25Q128") (pin "5") (pinfunction "SI_5") (pintype "bidirectional"))
      (node (ref "F1C100S") (pin "62") (pinfunction "PC3/SPI0_MOSI/UART0_TX_62") (pintype "passive"))
      (node (ref "PIN6") (pin "3") (pinfunction "3_3") (pintype "passive"))
    )
    (net (code "83") (name "/SVREF") (class "Default")
      (node (ref "C31") (pin "2") (pinfunction "2_2") (pintype "passive"))
      (node (ref "C37") (pin "1") (pinfunction "1_1") (pintype "passive"))
      (node (ref "F1C100S") (pin "33") (pinfunction "SVREF_33") (pintype "passive"))
      (node (ref "R23") (pin "1") (pinfunction "1_1") (pintype "passive"))
      (node (ref "R28") (pin "2") (pinfunction "2_2") (pintype "passive"))
    )
    (net (code "84") (name "/SYS_RESET") (class "Default")
      (node (ref "C36") (pin "1") (pinfunction "1_1") (pintype "passive"))
      (node (ref "F1C100S") (pin "70") (pinfunction "RESET_70") (pintype "passive"))
      (node (ref "J1") (pin "1") (pinfunction "1_1") (pintype "passive"))
      (node (ref "R22") (pin "2") (pinfunction "2_2") (pintype "passive"))
      (node (ref "S2") (pin "1") (pinfunction "1_1") (pintype "passive"))
    )
    (net (code "86") (name "/TV_IN0") (class "Default")
      (node (ref "F1C100S") (pin "78") (pinfunction "TVIN0_78") (pintype "passive"))
    )
    (net (code "87") (name "/TV_IN1") (class "Default")
      (node (ref "F1C100S") (pin "77") (pinfunction "TVIN1_77") (pintype "passive"))
    )
    (net (code "88") (name "/TV_OUT") (class "Default")
      (node (ref "F1C100S") (pin "72") (pinfunction "TVOUT_72") (pintype "passive"))
    )
    (net (code "89") (name "/TV_VRN") (class "Default")
      (node (ref "F1C100S") (pin "75") (pinfunction "TV_VRN_75") (pintype "passive"))
    )
    (net (code "90") (name "/TV_VRP") (class "Default")
      (node (ref "F1C100S") (pin "76") (pinfunction "TV_VRP_76") (pintype "passive"))
    )
    (net (code "91") (name "/USB_N") (class "Default")
      (node (ref "F1C100S") (pin "68") (pinfunction "USB_DM_68") (pintype "passive"))
      (node (ref "J*2") (pin "2") (pinfunction "Dm-_2") (pintype "passive"))
    )
    (net (code "92") (name "/USB_P") (class "Default")
      (node (ref "F1C100S") (pin "69") (pinfunction "USB_DP_69") (pintype "passive"))
      (node (ref "J*2") (pin "3") (pinfunction "Dp+_3") (pintype "passive"))
    )
    (net (code "93") (name "/VCC1.2V") (class "Default")
      (node (ref "F1C100S") (pin "22") (pinfunction "VDD-CORE_22") (pintype "passive"))
      (node (ref "F1C100S") (pin "35") (pinfunction "VDD-CORE_35") (pintype "passive"))
      (node (ref "F1C100S") (pin "71") (pinfunction "VDD-CORE_71") (pintype "passive"))
    )
    (net (code "94") (name "/VCC3.0V") (class "Default")
      (node (ref "F1C100S") (pin "80") (pinfunction "AVCC_80") (pintype "passive"))
    )
    (net (code "95") (name "/VCC3.3V_IN") (class "Default")
      (node (ref "PIN1") (pin "1") (pinfunction "1_1") (pintype "passive"))
      (node (ref "PIN1") (pin "2") (pinfunction "2_2") (pintype "passive"))
    )
    (net (code "96") (name "/VCC5V_IN") (class "Default")
      (node (ref "B1") (pin "2") (pinfunction "2_2") (pintype "passive"))
      (node (ref "J*1") (pin "1") (pinfunction "VCC_1") (pintype "passive"))
      (node (ref "J*2") (pin "1") (pinfunction "VCC_1") (pintype "passive"))
      (node (ref "PIN2") (pin "1") (pinfunction "1_1") (pintype "passive"))
      (node (ref "PIN2") (pin "2") (pinfunction "2_2") (pintype "passive"))
    )
    (net (code "97") (name "/VRA1") (class "Default")
      (node (ref "C34") (pin "1") (pinfunction "1_1") (pintype "passive"))
      (node (ref "F1C100S") (pin "81") (pinfunction "VRA1_81") (pintype "passive"))
      (node (ref "R25") (pin "2") (pinfunction "2_2") (pintype "passive"))
    )
    (net (code "98") (name "/VRA2") (class "Default")
      (node (ref "C35") (pin "1") (pinfunction "1_1") (pintype "passive"))
      (node (ref "F1C100S") (pin "83") (pinfunction "VRA2_83") (pintype "passive"))
      (node (ref "R26") (pin "2") (pinfunction "2_2") (pintype "passive"))
    )
    (net (code "107") (name "GND") (class "Default")
      (node (ref "25Q128") (pin "4") (pinfunction "GND_4") (pintype "passive"))
      (node (ref "B1") (pin "0") (pinfunction "GND_0") (pintype "passive"))
      (node (ref "C28") (pin "2") (pinfunction "2_2") (pintype "passive"))
      (node (ref "C29") (pin "1") (pinfunction "1_1") (pintype "passive"))
      (node (ref "C30") (pin "2") (pinfunction "2_2") (pintype "passive"))
      (node (ref "C32") (pin "1") (pinfunction "1_1") (pintype "passive"))
      (node (ref "C33") (pin "1") (pinfunction "1_1") (pintype "passive"))
      (node (ref "C34") (pin "2") (pinfunction "2_2") (pintype "passive"))
      (node (ref "C35") (pin "2") (pinfunction "2_2") (pintype "passive"))
      (node (ref "C36") (pin "2") (pinfunction "2_2") (pintype "passive"))
      (node (ref "C37") (pin "2") (pinfunction "2_2") (pintype "passive"))
      (node (ref "C38") (pin "2") (pinfunction "2_2") (pintype "passive"))
      (node (ref "C39") (pin "2") (pinfunction "2_2") (pintype "passive"))
      (node (ref "C40") (pin "2") (pinfunction "2_2") (pintype "passive"))
      (node (ref "C41") (pin "2") (pinfunction "2_2") (pintype "passive"))
      (node (ref "CH340E") (pin "3") (pinfunction "GND_3") (pintype "passive"))
      (node (ref "F1C100S") (pin "74") (pinfunction "TVGND_74") (pintype "passive"))
      (node (ref "F1C100S") (pin "82") (pinfunction "AGND_82") (pintype "passive"))
      (node (ref "F1C100S") (pin "89") (pinfunction "GND_89") (pintype "passive"))
      (node (ref "FPC1") (pin "30") (pinfunction "30_30") (pintype "passive"))
      (node (ref "FPC1") (pin "31") (pinfunction "31_31") (pintype "passive"))
      (node (ref "FPC1") (pin "32") (pinfunction "32_32") (pintype "passive"))
      (node (ref "J*1") (pin "0") (pinfunction "焊盘_0") (pintype "passive"))
      (node (ref "J*1") (pin "5") (pinfunction "GND_5") (pintype "passive"))
      (node (ref "J*2") (pin "0") (pinfunction "焊盘_0") (pintype "passive"))
      (node (ref "J*2") (pin "4") (pinfunction "ID_4") (pintype "passive"))
      (node (ref "J*2") (pin "5") (pinfunction "GND_5") (pintype "passive"))
      (node (ref "J1") (pin "7") (pinfunction "7_7") (pintype "passive"))
      (node (ref "J3") (pin "0") (pinfunction "0_0") (pintype "passive"))
      (node (ref "J4") (pin "0") (pinfunction "0_0") (pintype "passive"))
      (node (ref "J5") (pin "0") (pinfunction "0_0") (pintype "passive"))
      (node (ref "J6") (pin "0") (pinfunction "0_0") (pintype "passive"))
      (node (ref "LCD-通用-40pin") (pin "29") (pinfunction "29_29") (pintype "passive"))
      (node (ref "LCD-通用-40pin") (pin "3") (pinfunction "3_3") (pintype "passive"))
      (node (ref "LCD-通用-40pin") (pin "36") (pinfunction "36_36") (pintype "passive"))
      (node (ref "LCD-通用-40pin") (pin "41") (pinfunction "GND_41") (pintype "passive"))
      (node (ref "PIN1") (pin "3") (pinfunction "3_3") (pintype "passive"))
      (node (ref "PIN1") (pin "4") (pinfunction "4_4") (pintype "passive"))
      (node (ref "PIN2") (pin "3") (pinfunction "3_3") (pintype "passive"))
      (node (ref "PIN2") (pin "4") (pinfunction "4_4") (pintype "passive"))
      (node (ref "PIN6") (pin "4") (pinfunction "4_4") (pintype "passive"))
      (node (ref "PT4103") (pin "2") (pinfunction "GND_2") (pintype "passive"))
      (node (ref "R17") (pin "2") (pinfunction "2_2") (pintype "passive"))
      (node (ref "R18") (pin "2") (pinfunction "2_2") (pintype "passive"))
      (node (ref "R19") (pin "2") (pinfunction "2_2") (pintype "passive"))
      (node (ref "R25") (pin "1") (pinfunction "1_1") (pintype "passive"))
      (node (ref "R26") (pin "1") (pinfunction "1_1") (pintype "passive"))
      (node (ref "R28") (pin "1") (pinfunction "1_1") (pintype "passive"))
      (node (ref "R33") (pin "1") (pinfunction "1_1") (pintype "passive"))
      (node (ref "S1") (pin "2") (pinfunction "4_2") (pintype "passive"))
      (node (ref "S2") (pin "2") (pinfunction "4_2") (pintype "passive"))
      (node (ref "S3") (pin "2") (pinfunction "4_2") (pintype "passive"))
      (node (ref "S4") (pin "2") (pinfunction "4_2") (pintype "passive"))
      (node (ref "TF1") (pin "6") (pinfunction "VSS_6") (pintype "passive"))
      (node (ref "TF1") (pin "G") (pinfunction "GND_G") (pintype "passive"))
    )
    (net (code "108") (name "Net-(B1-Pad1)") (class "Default")
      (node (ref "B1") (pin "1") (pinfunction "1_1") (pintype "passive"))
      (node (ref "F2") (pin "1") (pinfunction "1_1") (pintype "passive"))
    )
    (net (code "109") (name "Net-(CH340E-RXD)") (class "Default")
      (node (ref "CH340E") (pin "9") (pinfunction "RXD_9") (pintype "passive"))
      (node (ref "R14") (pin "1") (pinfunction "1_1") (pintype "passive"))
    )
    (net (code "110") (name "Net-(CH340E-TXD)") (class "Default")
      (node (ref "1N4148") (pin "2") (pinfunction "2_2") (pintype "passive"))
      (node (ref "CH340E") (pin "8") (pinfunction "TXD_8") (pintype "passive"))
    )
    (net (code "111") (name "Net-(CH340E-V3)") (class "Default")
      (node (ref "C29") (pin "2") (pinfunction "2_2") (pintype "passive"))
      (node (ref "CH340E") (pin "10") (pinfunction "V3_10") (pintype "passive"))
    )
    (net (code "112") (name "Net-(LED-RGB-B)") (class "Default")
      (node (ref "LED-RGB") (pin "3") (pinfunction "B_3") (pintype "power_in"))
      (node (ref "R15") (pin "1") (pinfunction "1_1") (pintype "passive"))
    )
    (net (code "113") (name "Net-(LED-RGB-G)") (class "Default")
      (node (ref "LED-RGB") (pin "4") (pinfunction "G_4") (pintype "power_in"))
      (node (ref "R16") (pin "1") (pinfunction "1_1") (pintype "passive"))
    )
    (net (code "114") (name "Net-(LED-RGB-R)") (class "Default")
      (node (ref "LED-RGB") (pin "1") (pinfunction "R_1") (pintype "power_in"))
      (node (ref "R19") (pin "1") (pinfunction "1_1") (pintype "passive"))
    )
    (net (code "115") (name "Net-(PT4103-EN)") (class "Default")
      (node (ref "PT4103") (pin "4") (pinfunction "EN_4") (pintype "passive"))
      (node (ref "R31") (pin "1") (pinfunction "1_1") (pintype "passive"))
      (node (ref "R32") (pin "2") (pinfunction "2_2") (pintype "passive"))
    )
    (net (code "116") (name "Net-(PT4103-SW)") (class "Default")
      (node (ref "L8") (pin "2") (pinfunction "2_2") (pintype "passive"))
      (node (ref "PT4103") (pin "1") (pinfunction "SW_1") (pintype "passive"))
      (node (ref "SS41") (pin "1") (pinfunction "1_1") (pintype "passive"))
    )
    (net (code "117") (name "VCC2.5V") (class "Default")
      (node (ref "C31") (pin "1") (pinfunction "1_1") (pintype "passive"))
      (node (ref "F1C100S") (pin "30") (pinfunction "VCC-DRAM_30") (pintype "passive"))
      (node (ref "F1C100S") (pin "31") (pinfunction "VCC-DRAM_31") (pintype "passive"))
      (node (ref "F1C100S") (pin "32") (pinfunction "VCC-DRAM_32") (pintype "passive"))
      (node (ref "F1C100S") (pin "34") (pinfunction "VCC-DRAM_34") (pintype "passive"))
      (node (ref "F1C100S") (pin "36") (pinfunction "VCC-DRAM_36") (pintype "passive"))
      (node (ref "R23") (pin "2") (pinfunction "2_2") (pintype "passive"))
    )
    (net (code "118") (name "VCC3.3V") (class "Default")
      (node (ref "25Q128") (pin "3") (pinfunction "WP_3") (pintype "input"))
      (node (ref "25Q128") (pin "7") (pinfunction "HOLD_7") (pintype "input"))
      (node (ref "25Q128") (pin "8") (pinfunction "VCC_8") (pintype "power_in"))
      (node (ref "C28") (pin "1") (pinfunction "1_1") (pintype "passive"))
      (node (ref "C30") (pin "1") (pinfunction "1_1") (pintype "passive"))
      (node (ref "F1C100S") (pin "20") (pinfunction "VCC-IO_20") (pintype "passive"))
      (node (ref "F1C100S") (pin "4") (pinfunction "HPVCC_4") (pintype "passive"))
      (node (ref "F1C100S") (pin "5") (pinfunction "VCC-IO_5") (pintype "passive"))
      (node (ref "F1C100S") (pin "50") (pinfunction "VCC-IO_50") (pintype "passive"))
      (node (ref "F1C100S") (pin "67") (pinfunction "UVCC_67") (pintype "passive"))
      (node (ref "F1C100S") (pin "73") (pinfunction "TV_VCC_73") (pintype "passive"))
      (node (ref "FPC1") (pin "29") (pinfunction "29_29") (pintype "passive"))
      (node (ref "J1") (pin "6") (pinfunction "6_6") (pintype "passive"))
      (node (ref "LCD-通用-40pin") (pin "31") (pinfunction "31_31") (pintype "passive"))
      (node (ref "LCD-通用-40pin") (pin "4") (pinfunction "4_4") (pintype "passive"))
      (node (ref "LED-RGB") (pin "2") (pinfunction "+_2") (pintype "power_in"))
      (node (ref "R13") (pin "1") (pinfunction "1_1") (pintype "passive"))
      (node (ref "R17") (pin "1") (pinfunction "1_1") (pintype "passive"))
      (node (ref "R20") (pin "2") (pinfunction "2_2") (pintype "passive"))
      (node (ref "R21") (pin "2") (pinfunction "2_2") (pintype "passive"))
      (node (ref "R22") (pin "1") (pinfunction "1_1") (pintype "passive"))
      (node (ref "R24") (pin "2") (pinfunction "2_2") (pintype "passive"))
      (node (ref "R27") (pin "2") (pinfunction "2_2") (pintype "passive"))
      (node (ref "R29") (pin "2") (pinfunction "2_2") (pintype "passive"))
      (node (ref "R30") (pin "2") (pinfunction "2_2") (pintype "passive"))
      (node (ref "R32") (pin "1") (pinfunction "1_1") (pintype "passive"))
      (node (ref "TF1") (pin "4") (pinfunction "VDD_4") (pintype "passive"))
    )
    (net (code "119") (name "VCC5V") (class "Default")
      (node (ref "C38") (pin "1") (pinfunction "1_1") (pintype "passive"))
      (node (ref "C39") (pin "1") (pinfunction "1_1") (pintype "passive"))
      (node (ref "CH340E") (pin "7") (pinfunction "VCC_7") (pintype "passive"))
      (node (ref "F2") (pin "2") (pinfunction "2_2") (pintype "passive"))
      (node (ref "L8") (pin "1") (pinfunction "1_1") (pintype "passive"))
      (node (ref "PT4103") (pin "6") (pinfunction "IN_6") (pintype "passive"))
    )
    (net (code "120") (name "VLED+") (class "Default")
      (node (ref "C40") (pin "1") (pinfunction "1_1") (pintype "passive"))
      (node (ref "C41") (pin "1") (pinfunction "1_1") (pintype "passive"))
      (node (ref "LCD-通用-40pin") (pin "2") (pinfunction "2_2") (pintype "passive"))
      (node (ref "PT4103") (pin "5") (pinfunction "OV_5") (pintype "passive"))
      (node (ref "SS41") (pin "2") (pinfunction "2_2") (pintype "passive"))
      (node (ref "test7") (pin "1") (pinfunction "test_1") (pintype "passive"))
    )
    (net (code "121") (name "VLED-") (class "Default")
      (node (ref "LCD-通用-40pin") (pin "1") (pinfunction "1_1") (pintype "passive"))
      (node (ref "PT4103") (pin "3") (pinfunction "FB_3") (pintype "passive"))
      (node (ref "R33") (pin "2") (pinfunction "2_2") (pintype "passive"))
      (node (ref "test8") (pin "1") (pinfunction "test_1") (pintype "passive"))
    )
    (net (code "122") (name "unconnected-(B1-Pad3)") (class "Default")
      (node (ref "B1") (pin "3") (pinfunction "3_3") (pintype "passive"))
    )
    (net (code "123") (name "unconnected-(CH340E-CTS#-Pad5)") (class "Default")
      (node (ref "CH340E") (pin "5") (pinfunction "CTS#_5") (pintype "passive"))
    )
    (net (code "124") (name "unconnected-(CH340E-RTS#-Pad4)") (class "Default")
      (node (ref "CH340E") (pin "4") (pinfunction "RTS#_4") (pintype "passive"))
    )
    (net (code "125") (name "unconnected-(J*1-ID-Pad4)") (class "Default")
      (node (ref "J*1") (pin "4") (pinfunction "ID_4") (pintype "passive"))
    )
    (net (code "126") (name "unconnected-(LCD-通用-40pin-Pad35)") (class "Default")
      (node (ref "LCD-通用-40pin") (pin "35") (pinfunction "35_35") (pintype "passive"))
    )
  )
)
